# LED_SOP.net
KiCad netlist of a schematic drawn in Altium Designer
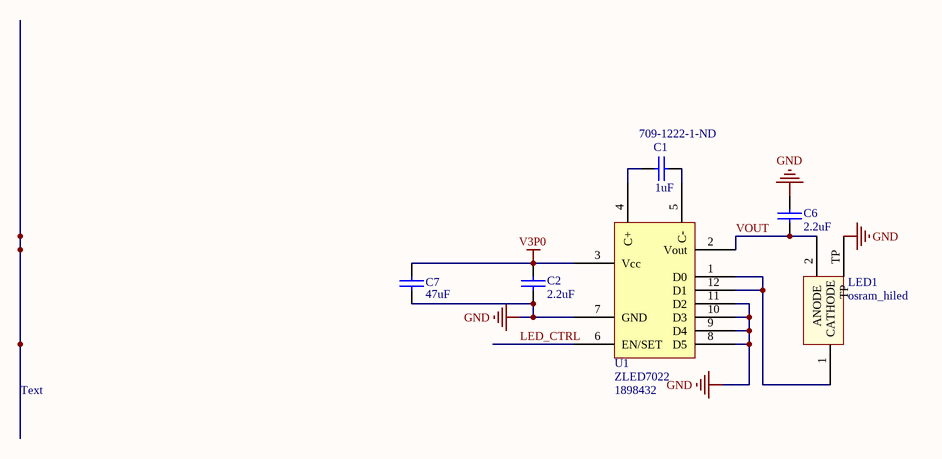
[diagram p0: LED_SOP.SchDoc]

(export (version "E")
  (design (tool "Eeschema 10.0.6"))
  (components
    (comp (ref "C1")
      (value "1uF")
      (footprint "0402s")
      (description "Capacitor")
      (fields
        (field (name "SUPPLIER PART NUMBER 1") "709-1222-1-ND")
        (field (name "MANUFACTURER") "Johanson Dielectrics Inc")
        (field (name "MANUFACTURER PART NUMBER") "100R07X105KV4T")
      )
      (libsource (lib "nRF24LE1F16Q24") (part "Cap"))
    )
    (comp (ref "C2")
      (value "2.2uF")
      (footprint "0402s")
      (description "Capacitor")
      (fields (field (name "Comment") "NP0 50V"))
      (libsource (lib "nRF24LE1F16Q24") (part "Cap"))
    )
    (comp (ref "C6")
      (value "2.2uF")
      (footprint "0402s")
      (description "Capacitor")
      (fields (field (name "Comment") "NP0 50V"))
      (libsource (lib "nRF24LE1F16Q24") (part "Cap"))
    )
    (comp (ref "C7")
      (value "47uF")
      (footprint "0402s")
      (description "Capacitor")
      (fields (field (name "Comment") "NP0 50V"))
      (libsource (lib "nRF24LE1F16Q24") (part "Cap"))
    )
    (comp (ref "LED1")
      (value "osram_hiled")
      (footprint "LUXEON LED")
      (libsource (lib "custom") (part "osram_hiled"))
    )
    (comp (ref "U1")
      (value "ZLED7022")
      (footprint "12utqfn")
      (description "ZLED 7022")
      (fields
        (field (name "SUPPLIER PART NUMBER 1") "1898432")
        (field (name "MANUFACTURER") "ZMDI")
        (field (name "MANUFACTURER PART NUMBER") "ZLED7022-ZI1R")
      )
      (libsource (lib "custom") (part "ZLED7022"))
    )
  )
  (nets
    (net (code "1") (name "/LED_CTRL") (class "Default")
      (node (ref "U1") (pin "6") (pinfunction "EN/SET_6") (pintype "passive"))
    )
    (net (code "2") (name "/VOUT") (class "Default")
      (node (ref "C6") (pin "1") (pintype "passive"))
      (node (ref "LED1") (pin "2") (pinfunction "ANODE_2") (pintype "passive"))
      (node (ref "U1") (pin "2") (pinfunction "Vout_2") (pintype "passive"))
    )
    (net (code "3") (name "GND") (class "Default")
      (node (ref "C2") (pin "1") (pintype "passive"))
      (node (ref "C6") (pin "2") (pintype "passive"))
      (node (ref "C7") (pin "1") (pintype "passive"))
      (node (ref "LED1") (pin "TP") (pinfunction "TP_TP") (pintype "passive"))
      (node (ref "U1") (pin "10") (pinfunction "D3_10") (pintype "passive"))
      (node (ref "U1") (pin "11") (pinfunction "D2_11") (pintype "passive"))
      (node (ref "U1") (pin "7") (pinfunction "GND_7") (pintype "passive"))
      (node (ref "U1") (pin "8") (pinfunction "D5_8") (pintype "passive"))
      (node (ref "U1") (pin "9") (pinfunction "D4_9") (pintype "passive"))
    )
    (net (code "4") (name "Net-(LED1-CATHODE)") (class "Default")
      (node (ref "LED1") (pin "1") (pinfunction "CATHODE_1") (pintype "passive"))
      (node (ref "U1") (pin "1") (pinfunction "D0_1") (pintype "passive"))
      (node (ref "U1") (pin "12") (pinfunction "D1_12") (pintype "passive"))
    )
    (net (code "5") (name "Net-(U1-C+)") (class "Default")
      (node (ref "C1") (pin "1") (pintype "passive"))
      (node (ref "U1") (pin "4") (pinfunction "C+_4") (pintype "passive"))
    )
    (net (code "6") (name "Net-(U1-C-)") (class "Default")
      (node (ref "C1") (pin "2") (pintype "passive"))
      (node (ref "U1") (pin "5") (pinfunction "C-_5") (pintype "passive"))
    )
    (net (code "7") (name "V3P0") (class "Default")
      (node (ref "C2") (pin "2") (pintype "passive"))
      (node (ref "C7") (pin "2") (pintype "passive"))
      (node (ref "U1") (pin "3") (pinfunction "Vcc_3") (pintype "passive"))
    )
  )
)
